# BuckReg.net
KiCad netlist of a schematic drawn in Altium Designer
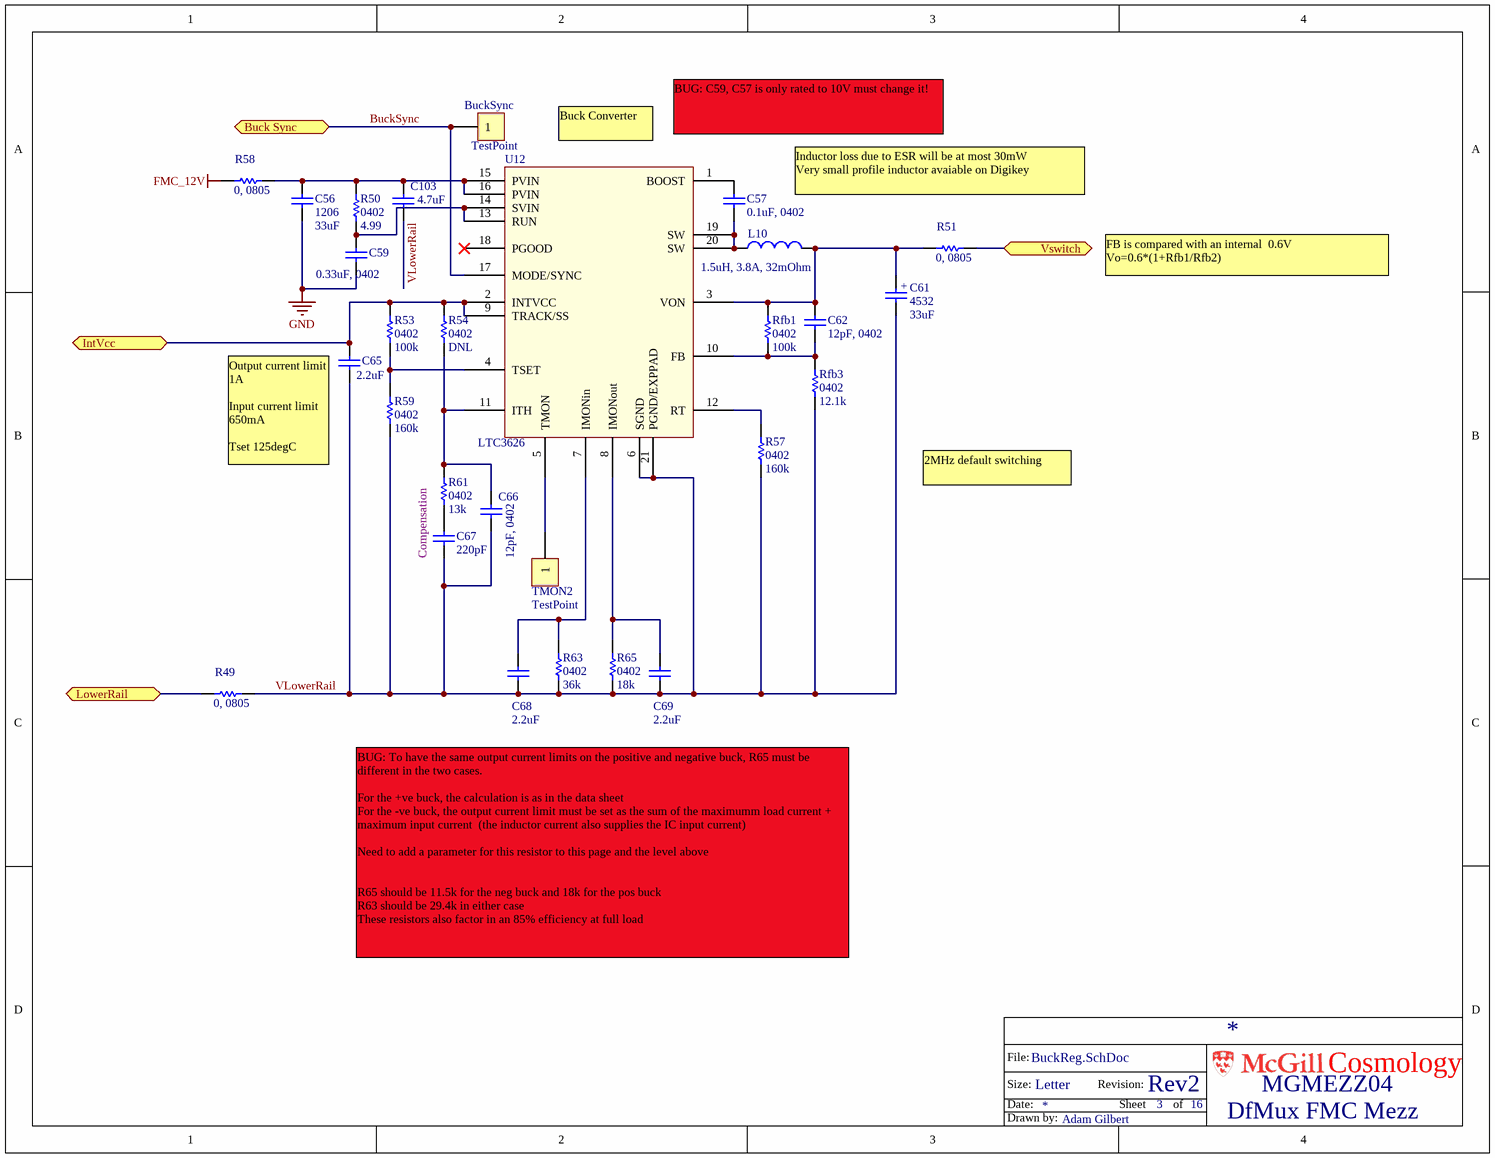
[diagram p0: BuckReg.SchDoc]

(export (version "E")
  (design (tool "Eeschema 10.0.6"))
  (components
    (comp (ref "BuckSync")
      (value "TestPoint")
      (footprint "TP-3520-SK")
      (description "TestPoint1")
      (libsource (lib "MGMEZZ04") (part "TestPoint"))
    )
    (comp (ref "C56")
      (value "33uF")
      (footprint "1206")
      (description "Capacitor, Ceramic, 1210")
      (fields (field (name "MANUFACTURER") "TDK Corporation"))
      (libsource (lib "MGMEZZ04") (part "CAP 1210"))
    )
    (comp (ref "C57")
      (value "0.1uF, 0402")
      (footprint "0402")
      (description "Capacitor, Ceramic, 0402")
      (fields (field (name "MANUFACTURER") "TDK Corporation"))
      (libsource (lib "MGMEZZ04") (part "CAP 0603"))
    )
    (comp (ref "C59")
      (value "0.33uF, 0402")
      (footprint "0402")
      (description "Capacitor, Ceramic, 0402")
      (fields (field (name "MANUFACTURER") "TDK Corporation"))
      (libsource (lib "MGMEZZ04") (part "CAP 0603"))
    )
    (comp (ref "C61")
      (value "33uF")
      (footprint "4532")
      (description "33u, 16V, 20%, 4532C, X5R")
      (fields (field (name "MANUFACTURER") "TDK Corporation"))
      (libsource (lib "MGMEZZ04") (part "CAP4532"))
    )
    (comp (ref "C62")
      (value "12pF, 0402")
      (footprint "0402")
      (description "Capacitor, Ceramic, 0402")
      (fields (field (name "MANUFACTURER") "Generic"))
      (libsource (lib "MGMEZZ04") (part "CAP 0402"))
    )
    (comp (ref "C65")
      (value "2.2uF")
      (footprint "0603")
      (description "Capacitor, Ceramic, 0603")
      (fields (field (name "MANUFACTURER") "Generic"))
      (libsource (lib "MGMEZZ04") (part "CAP 0603"))
    )
    (comp (ref "C66")
      (value "12pF, 0402")
      (footprint "0402")
      (description "Capacitor, Ceramic, 0402")
      (fields (field (name "MANUFACTURER") "Generic"))
      (libsource (lib "MGMEZZ04") (part "CAP 0402"))
    )
    (comp (ref "C67")
      (value "220pF")
      (footprint "0603")
      (description "Capacitor, Ceramic, 0603")
      (fields (field (name "MANUFACTURER") "Generic"))
      (libsource (lib "MGMEZZ04") (part "CAP 0603"))
    )
    (comp (ref "C68")
      (value "2.2uF")
      (footprint "0603")
      (description "Capacitor, Ceramic, 0603")
      (fields (field (name "MANUFACTURER") "TDK Corporation"))
      (libsource (lib "MGMEZZ04") (part "CAP 0603"))
    )
    (comp (ref "C69")
      (value "2.2uF")
      (footprint "0603")
      (description "Capacitor, Ceramic, 0603")
      (fields (field (name "MANUFACTURER") "TDK Corporation"))
      (libsource (lib "MGMEZZ04") (part "CAP 0603"))
    )
    (comp (ref "C103")
      (value "4.7uF")
      (footprint "0603")
      (description "Capacitor, Ceramic, 0603")
      (fields (field (name "MANUFACTURER") "Murata Electronics North America"))
      (libsource (lib "MGMEZZ04") (part "CAP 0603"))
    )
    (comp (ref "L10")
      (value "1.5uH")
      (footprint "IHLP-1212")
      (description "Inductor IHLP1212")
      (fields
        (field (name "MANUFACTURER") "Vishay Dale")
        (field (name "PART CONSTRAINTS") "1.5uH, 3.8A, 32mOhm")
      )
      (libsource (lib "MGMEZZ04") (part "IND IHLP1212"))
    )
    (comp (ref "R49")
      (value "0, 0805")
      (footprint "0805")
      (description "RES 0.0 OHM 1/8W 0805 SMD")
      (fields (field (name "MANUFACTURER") "e.g Vishay/Dale"))
      (libsource (lib "AdamsParts") (part "Res1812"))
    )
    (comp (ref "R50")
      (value "4.99")
      (footprint "0402")
      (description "Resistor")
      (fields (field (name "MANUFACTURER") "Generic"))
      (libsource (lib "MGMEZZ04") (part "RES 0402"))
    )
    (comp (ref "R51")
      (value "0, 0805")
      (footprint "0805")
      (description "RES 0.0 OHM 1/8W 0805 SMD")
      (fields (field (name "MANUFACTURER") "e.g Vishay/Dale"))
      (libsource (lib "AdamsParts") (part "Res1812"))
    )
    (comp (ref "R53")
      (value "100k")
      (footprint "0402")
      (description "Resistor")
      (fields (field (name "MANUFACTURER") "Generic"))
      (libsource (lib "MGMEZZ04") (part "RES 0402"))
    )
    (comp (ref "R54")
      (value "DNL")
      (footprint "0402")
      (description "Resistor")
      (fields (field (name "MANUFACTURER") "Generic"))
      (libsource (lib "MGMEZZ04") (part "RES 0402"))
    )
    (comp (ref "R57")
      (value "160k")
      (footprint "0402")
      (description "Resistor")
      (fields (field (name "MANUFACTURER") "Generic"))
      (libsource (lib "MGMEZZ04") (part "RES 0402"))
    )
    (comp (ref "R58")
      (value "0, 0805")
      (footprint "0805")
      (description "RES 0.0 OHM 1/8W 0805 SMD")
      (fields (field (name "MANUFACTURER") "e.g Vishay/Dale"))
      (libsource (lib "AdamsParts") (part "Res1812"))
    )
    (comp (ref "R59")
      (value "160k")
      (footprint "0402")
      (description "Resistor")
      (fields (field (name "MANUFACTURER") "Generic"))
      (libsource (lib "MGMEZZ04") (part "RES 0402"))
    )
    (comp (ref "R61")
      (value "13k")
      (footprint "0402")
      (description "Resistor")
      (fields (field (name "MANUFACTURER") "Generic"))
      (libsource (lib "MGMEZZ04") (part "RES 0402"))
    )
    (comp (ref "R63")
      (value "36k")
      (footprint "0402")
      (description "Resistor")
      (fields (field (name "MANUFACTURER") "Generic"))
      (libsource (lib "MGMEZZ04") (part "RES 0402"))
    )
    (comp (ref "R65")
      (value "18k")
      (footprint "0402")
      (description "Resistor")
      (fields (field (name "MANUFACTURER") "Generic"))
      (libsource (lib "MGMEZZ04") (part "RES 0402"))
    )
    (comp (ref "Rfb1")
      (value "100k")
      (footprint "0402")
      (description "Resistor")
      (fields (field (name "MANUFACTURER") "Generic"))
      (libsource (lib "MGMEZZ04") (part "RES 0402"))
    )
    (comp (ref "Rfb3")
      (value "12.1k")
      (footprint "0402")
      (description "Resistor")
      (fields (field (name "MANUFACTURER") "Generic"))
      (libsource (lib "MGMEZZ04") (part "RES 0402"))
    )
    (comp (ref "TMON2")
      (value "TestPoint")
      (footprint "TP-3520-SK")
      (description "TestPoint1")
      (libsource (lib "") (part "TestPoint_1"))
    )
    (comp (ref "U12")
      (value "LTC3626")
      (footprint "LTC3626")
      (description "20V, 2.5A Sync buck, 3Mhz")
      (fields (field (name "MANUFACTURER") "Linear Technology"))
      (libsource (lib "MGMEZZ04") (part "LTC3626"))
    )
  )
  (nets
    (net (code "1") (name "/BuckSync") (class "Default")
      (node (ref "BuckSync") (pin "1") (pinfunction "1_1") (pintype "passive"))
      (node (ref "U12") (pin "17") (pinfunction "MODE/SYNC_17") (pintype "passive"))
    )
    (net (code "2") (name "/IntVcc") (class "Default")
      (node (ref "C65") (pin "2") (pinfunction "2_2") (pintype "passive"))
      (node (ref "R53") (pin "1") (pinfunction "1_1") (pintype "passive"))
      (node (ref "R54") (pin "1") (pinfunction "1_1") (pintype "passive"))
      (node (ref "U12") (pin "2") (pinfunction "INTVCC_2") (pintype "passive"))
      (node (ref "U12") (pin "9") (pinfunction "TRACK/SS_9") (pintype "passive"))
    )
    (net (code "3") (name "/LowerRail") (class "Default")
      (node (ref "R49") (pin "2") (pinfunction "2_2") (pintype "passive"))
    )
    (net (code "4") (name "/VLowerRail") (class "Default")
      (node (ref "C103") (pin "2") (pinfunction "2_2") (pintype "passive"))
      (node (ref "C61") (pin "2") (pinfunction "2_2") (pintype "passive"))
      (node (ref "C65") (pin "1") (pinfunction "1_1") (pintype "passive"))
      (node (ref "C66") (pin "1") (pinfunction "1_1") (pintype "passive"))
      (node (ref "C67") (pin "2") (pinfunction "2_2") (pintype "passive"))
      (node (ref "C68") (pin "2") (pinfunction "2_2") (pintype "passive"))
      (node (ref "C69") (pin "2") (pinfunction "2_2") (pintype "passive"))
      (node (ref "R49") (pin "1") (pinfunction "1_1") (pintype "passive"))
      (node (ref "R57") (pin "2") (pinfunction "2_2") (pintype "passive"))
      (node (ref "R59") (pin "2") (pinfunction "2_2") (pintype "passive"))
      (node (ref "R63") (pin "2") (pinfunction "2_2") (pintype "passive"))
      (node (ref "R65") (pin "2") (pinfunction "2_2") (pintype "passive"))
      (node (ref "Rfb3") (pin "2") (pinfunction "2_2") (pintype "passive"))
      (node (ref "U12") (pin "21") (pinfunction "PGND/EXPPAD_21") (pintype "passive"))
      (node (ref "U12") (pin "6") (pinfunction "SGND_6") (pintype "passive"))
    )
    (net (code "5") (name "/Vswitch") (class "Default")
      (node (ref "R51") (pin "1") (pinfunction "1_1") (pintype "passive"))
    )
    (net (code "6") (name "FMC_12V") (class "Default")
      (node (ref "R58") (pin "2") (pinfunction "2_2") (pintype "passive"))
    )
    (net (code "7") (name "GND") (class "Default")
      (node (ref "C56") (pin "2") (pinfunction "2_2") (pintype "passive"))
      (node (ref "C59") (pin "1") (pinfunction "1_1") (pintype "passive"))
    )
    (net (code "8") (name "Net-(C57-Pad1)") (class "Default")
      (node (ref "C57") (pin "1") (pinfunction "1_1") (pintype "passive"))
      (node (ref "L10") (pin "1") (pinfunction "1_1") (pintype "passive"))
      (node (ref "U12") (pin "19") (pinfunction "SW_19") (pintype "passive"))
      (node (ref "U12") (pin "20") (pinfunction "SW_20") (pintype "passive"))
    )
    (net (code "9") (name "Net-(C67-Pad1)") (class "Default")
      (node (ref "C67") (pin "1") (pinfunction "1_1") (pintype "passive"))
      (node (ref "R61") (pin "2") (pinfunction "2_2") (pintype "passive"))
    )
    (net (code "10") (name "Net-(C103-Pad1)") (class "Default")
      (node (ref "C103") (pin "1") (pinfunction "1_1") (pintype "passive"))
      (node (ref "C56") (pin "1") (pinfunction "1_1") (pintype "passive"))
      (node (ref "R50") (pin "1") (pinfunction "1_1") (pintype "passive"))
      (node (ref "R58") (pin "1") (pinfunction "1_1") (pintype "passive"))
      (node (ref "U12") (pin "15") (pinfunction "PVIN_15") (pintype "passive"))
      (node (ref "U12") (pin "16") (pinfunction "PVIN_16") (pintype "passive"))
    )
    (net (code "11") (name "Net-(U12-BOOST)") (class "Default")
      (node (ref "C57") (pin "2") (pinfunction "2_2") (pintype "passive"))
      (node (ref "U12") (pin "1") (pinfunction "BOOST_1") (pintype "passive"))
    )
    (net (code "12") (name "Net-(U12-FB)") (class "Default")
      (node (ref "C62") (pin "1") (pinfunction "1_1") (pintype "passive"))
      (node (ref "Rfb1") (pin "2") (pinfunction "2_2") (pintype "passive"))
      (node (ref "Rfb3") (pin "1") (pinfunction "1_1") (pintype "passive"))
      (node (ref "U12") (pin "10") (pinfunction "FB_10") (pintype "passive"))
    )
    (net (code "13") (name "Net-(U12-IMONin)") (class "Default")
      (node (ref "C68") (pin "1") (pinfunction "1_1") (pintype "passive"))
      (node (ref "R63") (pin "1") (pinfunction "1_1") (pintype "passive"))
      (node (ref "U12") (pin "7") (pinfunction "IMONin_7") (pintype "passive"))
    )
    (net (code "14") (name "Net-(U12-IMONout)") (class "Default")
      (node (ref "C69") (pin "1") (pinfunction "1_1") (pintype "passive"))
      (node (ref "R65") (pin "1") (pinfunction "1_1") (pintype "passive"))
      (node (ref "U12") (pin "8") (pinfunction "IMONout_8") (pintype "passive"))
    )
    (net (code "15") (name "Net-(U12-ITH)") (class "Default")
      (node (ref "C66") (pin "2") (pinfunction "2_2") (pintype "passive"))
      (node (ref "R54") (pin "2") (pinfunction "2_2") (pintype "passive"))
      (node (ref "R61") (pin "1") (pinfunction "1_1") (pintype "passive"))
      (node (ref "U12") (pin "11") (pinfunction "ITH_11") (pintype "passive"))
    )
    (net (code "16") (name "Net-(U12-RT)") (class "Default")
      (node (ref "R57") (pin "1") (pinfunction "1_1") (pintype "passive"))
      (node (ref "U12") (pin "12") (pinfunction "RT_12") (pintype "passive"))
    )
    (net (code "17") (name "Net-(U12-RUN)") (class "Default")
      (node (ref "C59") (pin "2") (pinfunction "2_2") (pintype "passive"))
      (node (ref "R50") (pin "2") (pinfunction "2_2") (pintype "passive"))
      (node (ref "U12") (pin "13") (pinfunction "RUN_13") (pintype "passive"))
      (node (ref "U12") (pin "14") (pinfunction "SVIN_14") (pintype "passive"))
    )
    (net (code "18") (name "Net-(U12-TMON)") (class "Default")
      (node (ref "TMON2") (pin "1") (pinfunction "1_1") (pintype "passive"))
      (node (ref "U12") (pin "5") (pinfunction "TMON_5") (pintype "passive"))
    )
    (net (code "19") (name "Net-(U12-TSET)") (class "Default")
      (node (ref "R53") (pin "2") (pinfunction "2_2") (pintype "passive"))
      (node (ref "R59") (pin "1") (pinfunction "1_1") (pintype "passive"))
      (node (ref "U12") (pin "4") (pinfunction "TSET_4") (pintype "passive"))
    )
    (net (code "20") (name "Net-(U12-VON)") (class "Default")
      (node (ref "C61") (pin "1") (pinfunction "1_1") (pintype "passive"))
      (node (ref "C62") (pin "2") (pinfunction "2_2") (pintype "passive"))
      (node (ref "L10") (pin "2") (pinfunction "2_2") (pintype "passive"))
      (node (ref "R51") (pin "2") (pinfunction "2_2") (pintype "passive"))
      (node (ref "Rfb1") (pin "1") (pinfunction "1_1") (pintype "passive"))
      (node (ref "U12") (pin "3") (pinfunction "VON_3") (pintype "passive"))
    )
    (net (code "21") (name "unconnected-(U12-PGOOD-Pad18)") (class "Default")
      (node (ref "U12") (pin "18") (pinfunction "PGOOD_18") (pintype "passive+no_connect"))
    )
  )
)
